# 1_81_Grayscale_OLED_Breakout.net
KiCad netlist of a schematic drawn in EAGLE
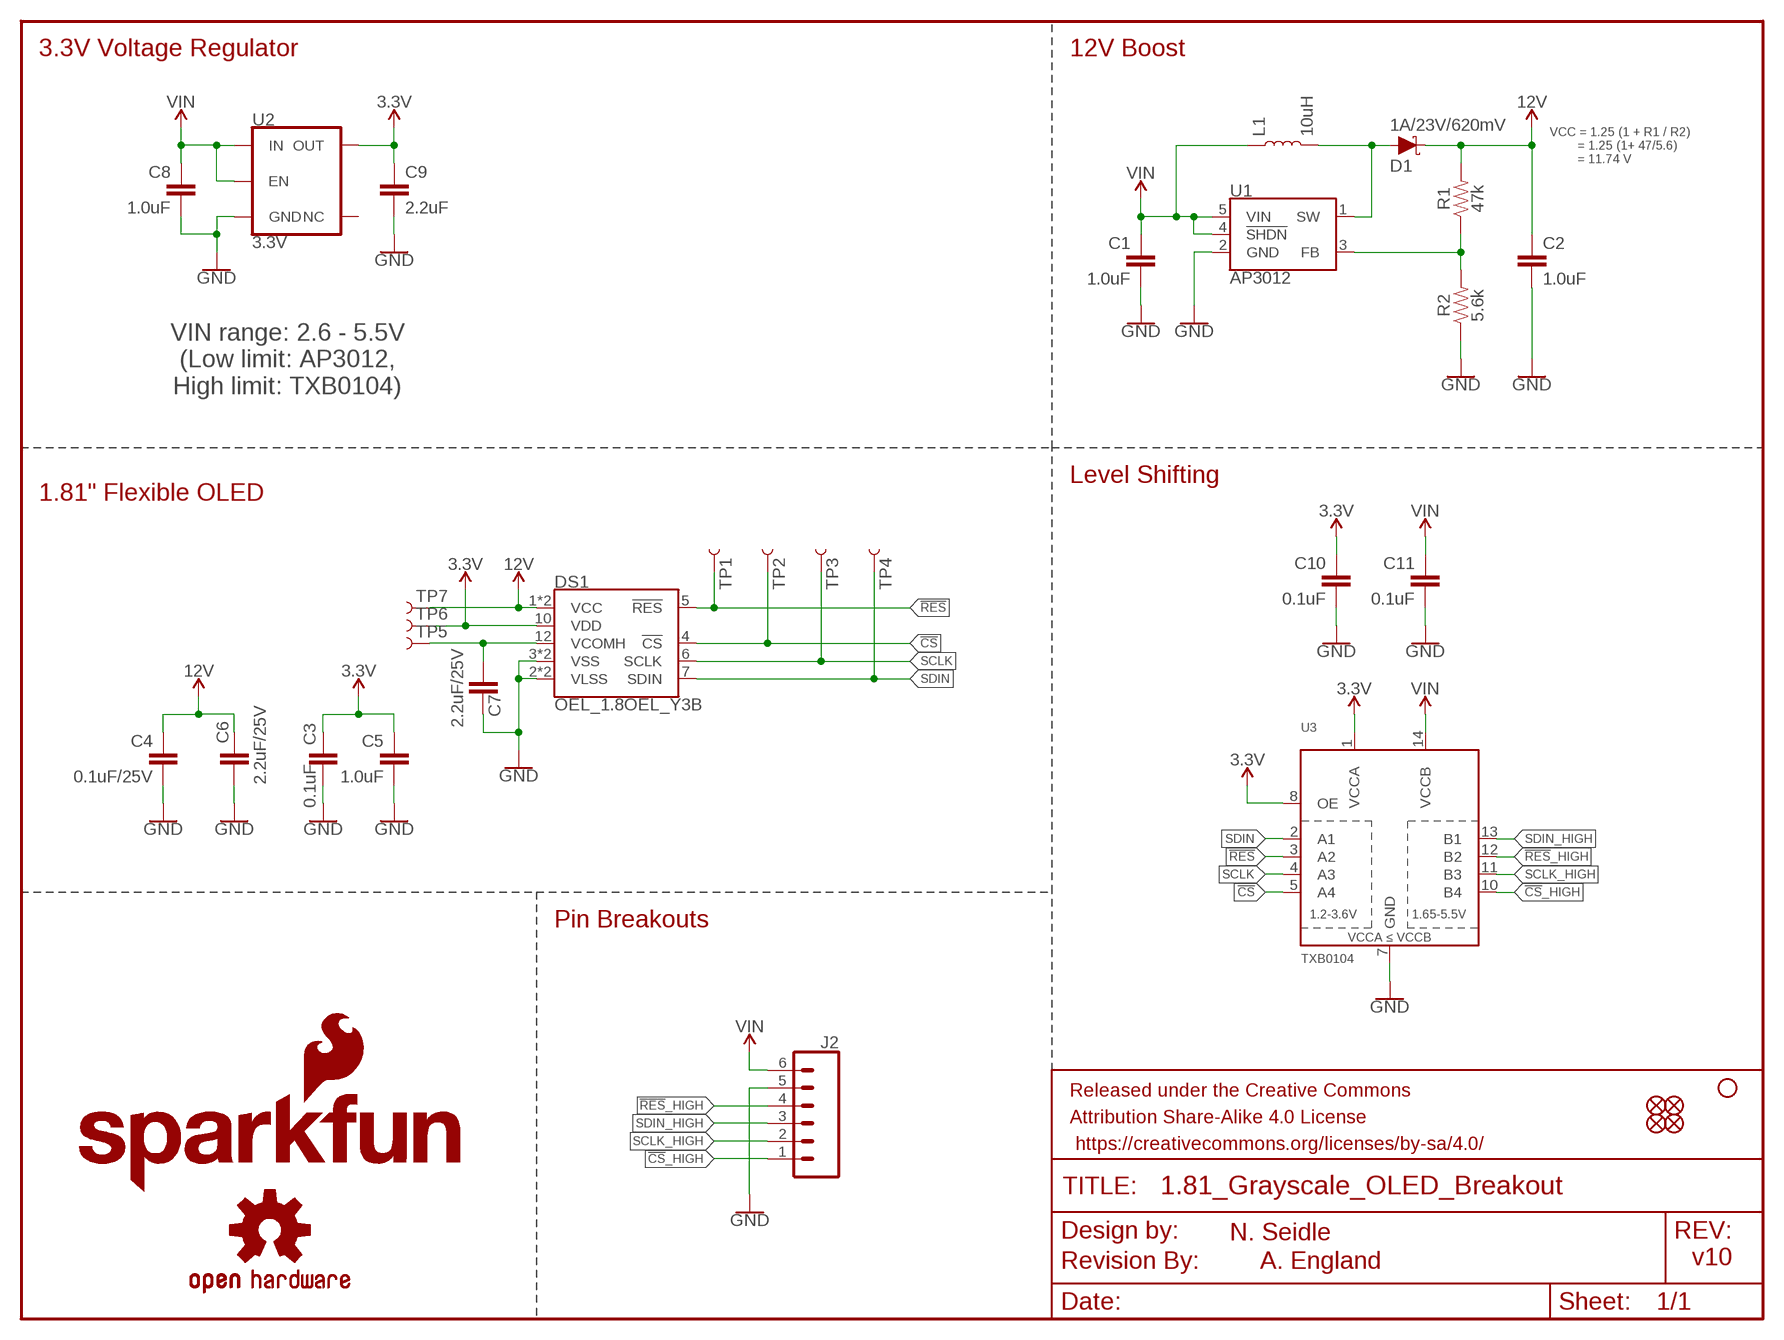
[diagram p0: schematic, sheet 1]

(export (version "E")
  (design (tool "Eeschema 10.0.6"))
  (components
    (comp (ref "C1")
      (value "1.0uF")
      (footprint "eagle-import:0603")
      (libsource (lib "eagle-import") (part "1.0UF-0603-16V-10%"))
    )
    (comp (ref "C2")
      (value "1.0uF")
      (footprint "eagle-import:0805")
      (libsource (lib "eagle-import") (part "1.0UF-0805-25V-10%"))
    )
    (comp (ref "C3")
      (value "0.1uF")
      (footprint "eagle-import:0603")
      (libsource (lib "eagle-import") (part "0.1UF-0603-25V-(+80/-20%)"))
    )
    (comp (ref "C4")
      (value "0.1uF/25V")
      (footprint "eagle-import:0603")
      (libsource (lib "eagle-import") (part "0.1UF-0603-25V-(+80/-20%)"))
    )
    (comp (ref "C5")
      (value "1.0uF")
      (footprint "eagle-import:0603")
      (libsource (lib "eagle-import") (part "1.0UF-0603-16V-10%"))
    )
    (comp (ref "C6")
      (value "2.2uF/25V")
      (footprint "eagle-import:0805")
      (libsource (lib "eagle-import") (part "2.2UF-0805-25V-(+80/-20%)"))
    )
    (comp (ref "C7")
      (value "2.2uF/25V")
      (footprint "eagle-import:0805")
      (libsource (lib "eagle-import") (part "2.2UF-0805-25V-(+80/-20%)"))
    )
    (comp (ref "C8")
      (value "1.0uF")
      (footprint "eagle-import:0603")
      (libsource (lib "eagle-import") (part "1.0UF-0603-16V-10%"))
    )
    (comp (ref "C9")
      (value "2.2uF")
      (footprint "eagle-import:0603")
      (libsource (lib "eagle-import") (part "2.2UF-0603-10V-20%"))
    )
    (comp (ref "C10")
      (value "0.1uF")
      (footprint "eagle-import:0603")
      (libsource (lib "eagle-import") (part "0.1UF-0603-25V-(+80/-20%)"))
    )
    (comp (ref "C11")
      (value "0.1uF")
      (footprint "eagle-import:0603")
      (libsource (lib "eagle-import") (part "0.1UF-0603-25V-(+80/-20%)"))
    )
    (comp (ref "D1")
      (value "1A/23V/620mV")
      (footprint "eagle-import:SOD-323")
      (libsource (lib "eagle-import") (part "DIODE-SCHOTTKY-BAT20J"))
    )
    (comp (ref "DS1")
      (value "OEL_1.8OEL_Y3B")
      (footprint "eagle-import:OEL_1.8_FPC_Y3B")
      (libsource (lib "eagle-import") (part "OEL_1.8OEL_Y3B"))
    )
    (comp (ref "FD1")
      (value "FIDUCIAL1X2")
      (footprint "eagle-import:FIDUCIAL-1X2")
      (libsource (lib "eagle-import") (part "FIDUCIAL1X2"))
    )
    (comp (ref "FD2")
      (value "FIDUCIAL1X2")
      (footprint "eagle-import:FIDUCIAL-1X2")
      (libsource (lib "eagle-import") (part "FIDUCIAL1X2"))
    )
    (comp (ref "FD3")
      (value "FIDUCIAL1X2")
      (footprint "eagle-import:FIDUCIAL-1X2")
      (libsource (lib "eagle-import") (part "FIDUCIAL1X2"))
    )
    (comp (ref "FD4")
      (value "FIDUCIAL1X2")
      (footprint "eagle-import:FIDUCIAL-1X2")
      (libsource (lib "eagle-import") (part "FIDUCIAL1X2"))
    )
    (comp (ref "FRAME1")
      (value "FRAME-LETTER")
      (footprint "eagle-import:CREATIVE_COMMONS")
      (libsource (lib "eagle-import") (part "FRAME-LETTER"))
    )
    (comp (ref "H2")
      (value "STAND-OFF")
      (footprint "eagle-import:STAND-OFF")
      (libsource (lib "eagle-import") (part "STAND-OFF"))
    )
    (comp (ref "J2")
      (value "CONN_06NO_SILK_NO_POP")
      (footprint "eagle-import:1X06_NO_SILK")
      (libsource (lib "eagle-import") (part "CONN_06NO_SILK_NO_POP"))
    )
    (comp (ref "L1")
      (value "10uH")
      (footprint "eagle-import:INDUCTOR_4.7UH")
      (libsource (lib "eagle-import") (part "INDUCTOR-CDRH-10UH"))
    )
    (comp (ref "LOGO1")
      (value "SFE_LOGO_NAME_FLAME.1_INCH")
      (footprint "eagle-import:SFE_LOGO_NAME_FLAME_.1")
      (libsource (lib "eagle-import") (part "SFE_LOGO_NAME_FLAME.1_INCH"))
    )
    (comp (ref "LOGO2")
      (value "REVISION")
      (footprint "eagle-import:REVISION")
      (libsource (lib "eagle-import") (part "REVISION"))
    )
    (comp (ref "LOGO3")
      (value "SFE_LOGO_FLAME.1_INCH")
      (footprint "eagle-import:SFE_LOGO_FLAME_.1")
      (libsource (lib "eagle-import") (part "SFE_LOGO_FLAME.1_INCH"))
    )
    (comp (ref "LOGO4")
      (value "OSHW-LOGOS")
      (footprint "eagle-import:OSHW-LOGO-S")
      (libsource (lib "eagle-import") (part "OSHW-LOGOS"))
    )
    (comp (ref "R1")
      (value "47k")
      (footprint "eagle-import:0603")
      (libsource (lib "eagle-import") (part "47KOHM-0603-1/10W-1%"))
    )
    (comp (ref "R2")
      (value "5.6k")
      (footprint "eagle-import:0603")
      (libsource (lib "eagle-import") (part "5.6KOHM-0603-1/10W-1%"))
    )
    (comp (ref "TP1")
      (value "TEST-POINT3")
      (footprint "eagle-import:PAD.03X.03")
      (libsource (lib "eagle-import") (part "TEST-POINT3"))
    )
    (comp (ref "TP2")
      (value "TEST-POINT3")
      (footprint "eagle-import:PAD.03X.03")
      (libsource (lib "eagle-import") (part "TEST-POINT3"))
    )
    (comp (ref "TP3")
      (value "TEST-POINT3")
      (footprint "eagle-import:PAD.03X.03")
      (libsource (lib "eagle-import") (part "TEST-POINT3"))
    )
    (comp (ref "TP4")
      (value "TEST-POINT3")
      (footprint "eagle-import:PAD.03X.03")
      (libsource (lib "eagle-import") (part "TEST-POINT3"))
    )
    (comp (ref "TP5")
      (value "TEST-POINT3")
      (footprint "eagle-import:PAD.03X.03")
      (libsource (lib "eagle-import") (part "TEST-POINT3"))
    )
    (comp (ref "TP6")
      (value "TEST-POINT3")
      (footprint "eagle-import:PAD.03X.03")
      (libsource (lib "eagle-import") (part "TEST-POINT3"))
    )
    (comp (ref "TP7")
      (value "TEST-POINT3")
      (footprint "eagle-import:PAD.03X.03")
      (libsource (lib "eagle-import") (part "TEST-POINT3"))
    )
    (comp (ref "U1")
      (value "AP3012")
      (footprint "eagle-import:SOT23-5")
      (libsource (lib "eagle-import") (part "AP3012"))
    )
    (comp (ref "U2")
      (value "3.3V")
      (footprint "eagle-import:SOT23-5")
      (libsource (lib "eagle-import") (part "V_REG_AP2112K-3.3V"))
    )
    (comp (ref "U3")
      (value "TXB0104")
      (footprint "eagle-import:SO14")
      (libsource (lib "eagle-import") (part "TXB0104PWRSOIC14"))
    )
  )
  (nets
    (net (code "1") (name "/~{CS}") (class "Default")
      (node (ref "DS1") (pin "4") (pinfunction "~{CS}_4") (pintype "bidirectional"))
      (node (ref "TP2") (pin "P$1") (pinfunction "1_P$1") (pintype "bidirectional"))
      (node (ref "U3") (pin "5") (pinfunction "A4_5") (pintype "bidirectional"))
    )
    (net (code "2") (name "/~{CS}_HIGH") (class "Default")
      (node (ref "J2") (pin "1") (pinfunction "1_1") (pintype "passive"))
      (node (ref "U3") (pin "10") (pinfunction "B4_10") (pintype "bidirectional"))
    )
    (net (code "3") (name "/~{RES}") (class "Default")
      (node (ref "DS1") (pin "5") (pinfunction "~{RES}_5") (pintype "bidirectional"))
      (node (ref "TP1") (pin "P$1") (pinfunction "1_P$1") (pintype "bidirectional"))
      (node (ref "U3") (pin "3") (pinfunction "A2_3") (pintype "bidirectional"))
    )
    (net (code "4") (name "/~{RES}_HIGH") (class "Default")
      (node (ref "J2") (pin "4") (pinfunction "4_4") (pintype "passive"))
      (node (ref "U3") (pin "12") (pinfunction "B2_12") (pintype "bidirectional"))
    )
    (net (code "5") (name "3.3V") (class "Default")
      (node (ref "C10") (pin "1") (pinfunction "1_1") (pintype "passive"))
      (node (ref "C3") (pin "1") (pinfunction "1_1") (pintype "passive"))
      (node (ref "C5") (pin "1") (pinfunction "1_1") (pintype "passive"))
      (node (ref "C9") (pin "1") (pinfunction "1_1") (pintype "passive"))
      (node (ref "DS1") (pin "10") (pinfunction "VDD_10") (pintype "bidirectional"))
      (node (ref "TP6") (pin "P$1") (pinfunction "1_P$1") (pintype "bidirectional"))
      (node (ref "U2") (pin "5") (pinfunction "OUT_5") (pintype "passive"))
      (node (ref "U3") (pin "1") (pinfunction "VCCA_1") (pintype "bidirectional"))
      (node (ref "U3") (pin "8") (pinfunction "OE_8") (pintype "bidirectional"))
    )
    (net (code "6") (name "12V") (class "Default")
      (node (ref "C2") (pin "1") (pinfunction "1_1") (pintype "passive"))
      (node (ref "C4") (pin "1") (pinfunction "1_1") (pintype "passive"))
      (node (ref "C6") (pin "1") (pinfunction "1_1") (pintype "passive"))
      (node (ref "D1") (pin "C") (pinfunction "C_C") (pintype "passive"))
      (node (ref "DS1") (pin "1") (pinfunction "VCC_1") (pintype "bidirectional"))
      (node (ref "DS1") (pin "13") (pinfunction "VCC_13") (pintype "bidirectional"))
      (node (ref "R1") (pin "2") (pinfunction "2_2") (pintype "passive"))
      (node (ref "TP7") (pin "P$1") (pinfunction "1_P$1") (pintype "bidirectional"))
    )
    (net (code "7") (name "GND") (class "Default")
      (node (ref "C1") (pin "2") (pinfunction "2_2") (pintype "passive"))
      (node (ref "C10") (pin "2") (pinfunction "2_2") (pintype "passive"))
      (node (ref "C11") (pin "2") (pinfunction "2_2") (pintype "passive"))
      (node (ref "C2") (pin "2") (pinfunction "2_2") (pintype "passive"))
      (node (ref "C3") (pin "2") (pinfunction "2_2") (pintype "passive"))
      (node (ref "C4") (pin "2") (pinfunction "2_2") (pintype "passive"))
      (node (ref "C5") (pin "2") (pinfunction "2_2") (pintype "passive"))
      (node (ref "C6") (pin "2") (pinfunction "2_2") (pintype "passive"))
      (node (ref "C7") (pin "1") (pinfunction "1_1") (pintype "passive"))
      (node (ref "C8") (pin "2") (pinfunction "2_2") (pintype "passive"))
      (node (ref "C9") (pin "2") (pinfunction "2_2") (pintype "passive"))
      (node (ref "DS1") (pin "2") (pinfunction "VLSS_2") (pintype "bidirectional"))
      (node (ref "DS1") (pin "3") (pinfunction "VSS_3") (pintype "bidirectional"))
      (node (ref "DS1") (pin "8") (pinfunction "VSS_8") (pintype "bidirectional"))
      (node (ref "DS1") (pin "9") (pinfunction "VLSS_9") (pintype "bidirectional"))
      (node (ref "J2") (pin "5") (pinfunction "5_5") (pintype "passive"))
      (node (ref "R2") (pin "1") (pinfunction "1_1") (pintype "passive"))
      (node (ref "U1") (pin "2") (pinfunction "GND_2") (pintype "bidirectional"))
      (node (ref "U2") (pin "2") (pinfunction "GND_2") (pintype "input"))
      (node (ref "U3") (pin "7") (pinfunction "GND_7") (pintype "bidirectional"))
    )
    (net (code "8") (name "Net-(DS1-VCOMH)") (class "Default")
      (node (ref "C7") (pin "2") (pinfunction "2_2") (pintype "passive"))
      (node (ref "DS1") (pin "12") (pinfunction "VCOMH_12") (pintype "bidirectional"))
      (node (ref "TP5") (pin "P$1") (pinfunction "1_P$1") (pintype "bidirectional"))
    )
    (net (code "9") (name "Net-(L1-2)") (class "Default")
      (node (ref "D1") (pin "A") (pinfunction "A_A") (pintype "passive"))
      (node (ref "L1") (pin "P$2") (pinfunction "2_P$2") (pintype "passive"))
      (node (ref "U1") (pin "1") (pinfunction "SW_1") (pintype "bidirectional"))
    )
    (net (code "10") (name "Net-(U1-FB)") (class "Default")
      (node (ref "R1") (pin "1") (pinfunction "1_1") (pintype "passive"))
      (node (ref "R2") (pin "2") (pinfunction "2_2") (pintype "passive"))
      (node (ref "U1") (pin "3") (pinfunction "FB_3") (pintype "bidirectional"))
    )
    (net (code "11") (name "SCLK") (class "Default")
      (node (ref "DS1") (pin "6") (pinfunction "SCLK_6") (pintype "bidirectional"))
      (node (ref "TP3") (pin "P$1") (pinfunction "1_P$1") (pintype "bidirectional"))
      (node (ref "U3") (pin "4") (pinfunction "A3_4") (pintype "bidirectional"))
    )
    (net (code "12") (name "SCLK_HIGH") (class "Default")
      (node (ref "J2") (pin "2") (pinfunction "2_2") (pintype "passive"))
      (node (ref "U3") (pin "11") (pinfunction "B3_11") (pintype "bidirectional"))
    )
    (net (code "13") (name "SDIN") (class "Default")
      (node (ref "DS1") (pin "7") (pinfunction "SDIN_7") (pintype "bidirectional"))
      (node (ref "TP4") (pin "P$1") (pinfunction "1_P$1") (pintype "bidirectional"))
      (node (ref "U3") (pin "2") (pinfunction "A1_2") (pintype "bidirectional"))
    )
    (net (code "14") (name "SDIN_HIGH") (class "Default")
      (node (ref "J2") (pin "3") (pinfunction "3_3") (pintype "passive"))
      (node (ref "U3") (pin "13") (pinfunction "B1_13") (pintype "bidirectional"))
    )
    (net (code "15") (name "VIN") (class "Default")
      (node (ref "C1") (pin "1") (pinfunction "1_1") (pintype "passive"))
      (node (ref "C11") (pin "1") (pinfunction "1_1") (pintype "passive"))
      (node (ref "C8") (pin "1") (pinfunction "1_1") (pintype "passive"))
      (node (ref "J2") (pin "6") (pinfunction "6_6") (pintype "passive"))
      (node (ref "L1") (pin "P$1") (pinfunction "1_P$1") (pintype "passive"))
      (node (ref "U1") (pin "4") (pinfunction "~{SHDN}_4") (pintype "bidirectional"))
      (node (ref "U1") (pin "5") (pinfunction "VIN_5") (pintype "bidirectional"))
      (node (ref "U2") (pin "1") (pinfunction "IN_1") (pintype "input"))
      (node (ref "U2") (pin "3") (pinfunction "EN_3") (pintype "input"))
      (node (ref "U3") (pin "14") (pinfunction "VCCB_14") (pintype "bidirectional"))
    )
    (net (code "16") (name "unconnected-(U2-NC-Pad4)") (class "Default")
      (node (ref "U2") (pin "4") (pinfunction "NC_4") (pintype "no_connect"))
    )
  )
)
